# Commodore_CPM_Modul.net
KiCad netlist of a schematic drawn in Altium Designer
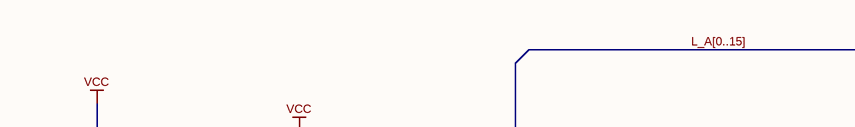
[diagram p0: Commodore CPM Modul.SchDoc, top left]
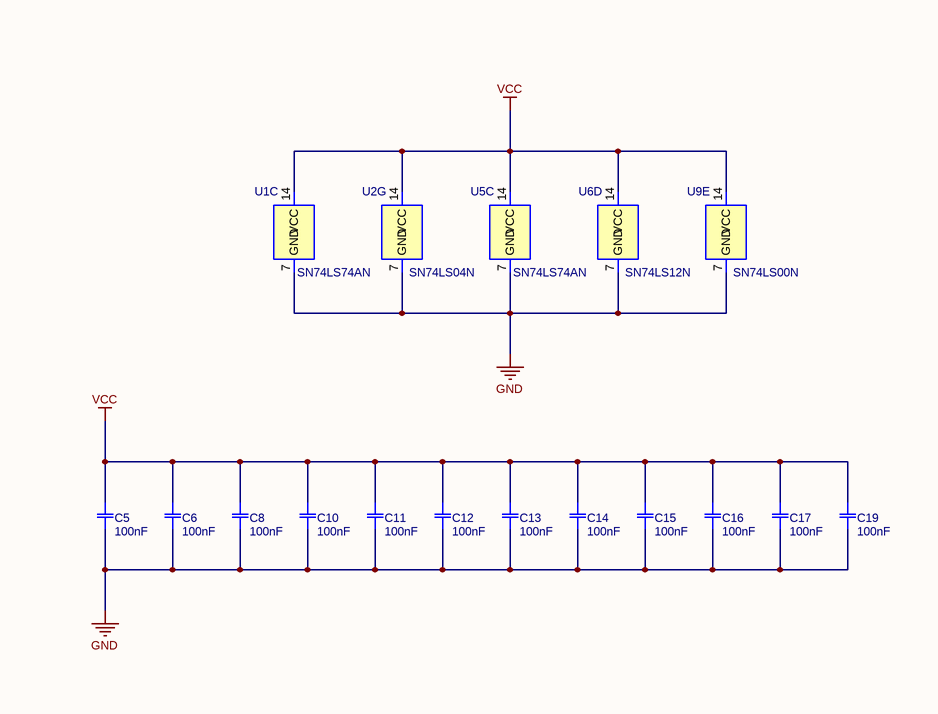
[diagram p1: Commodore CPM Modul.SchDoc, top right]
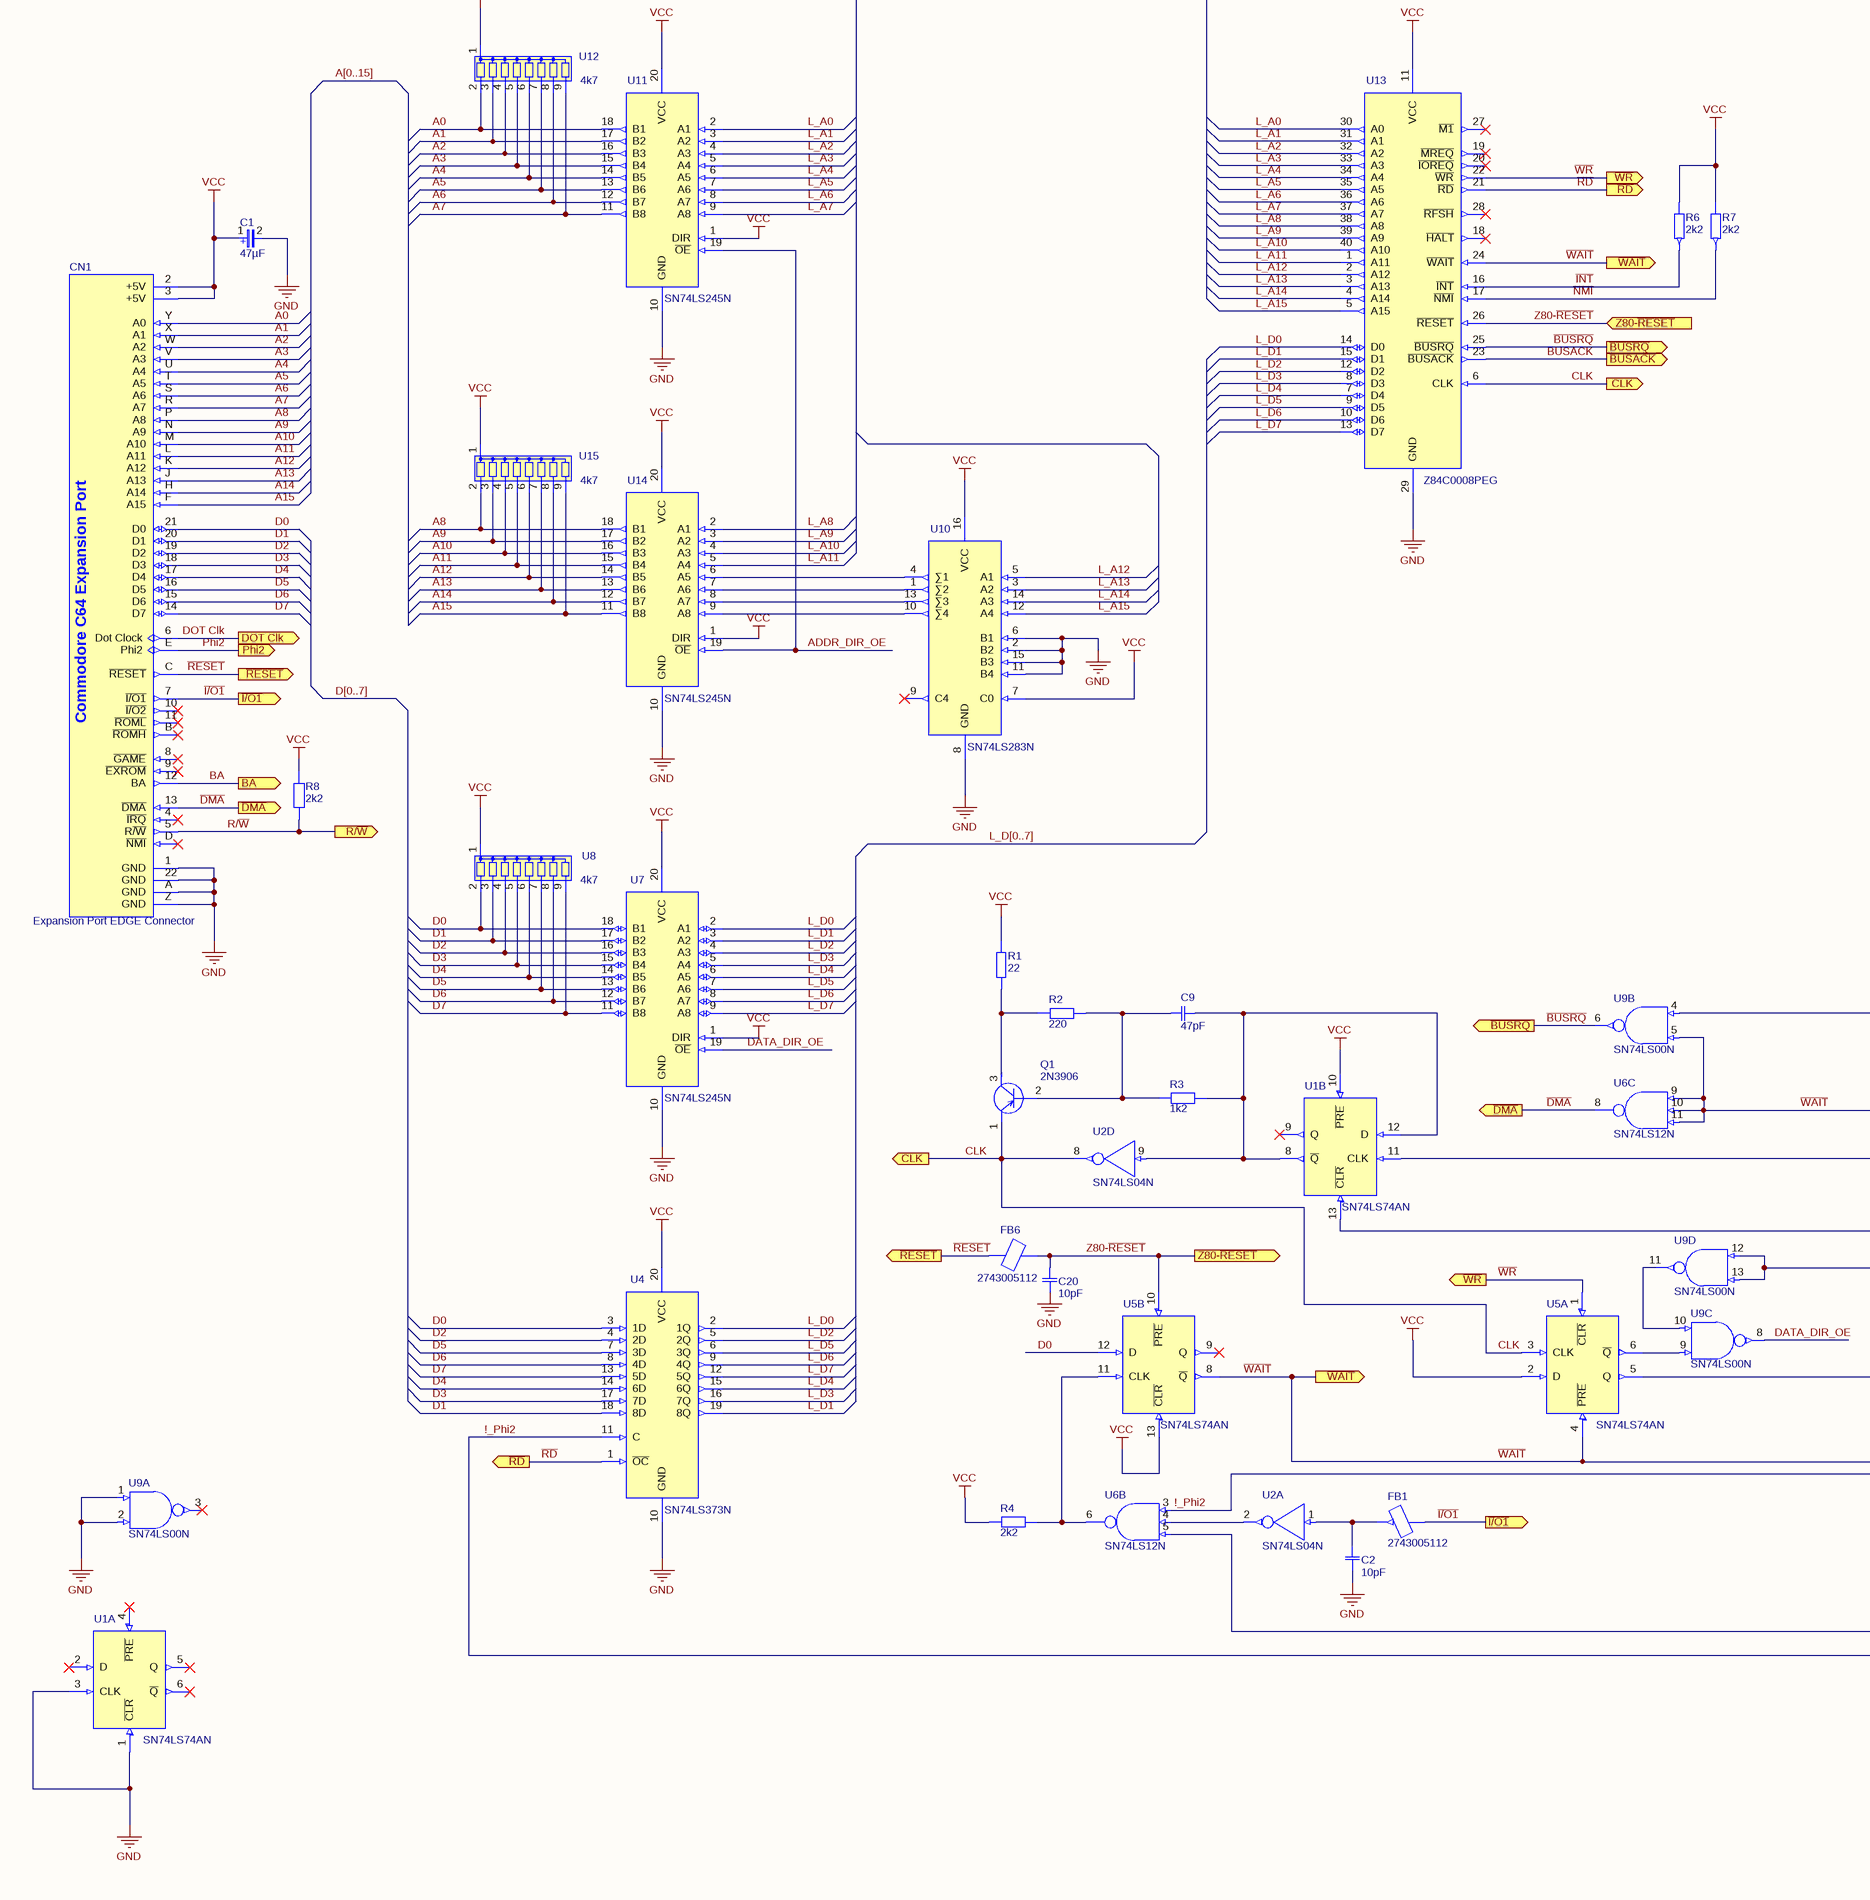
[diagram p2: Commodore CPM Modul.SchDoc, bottom left]
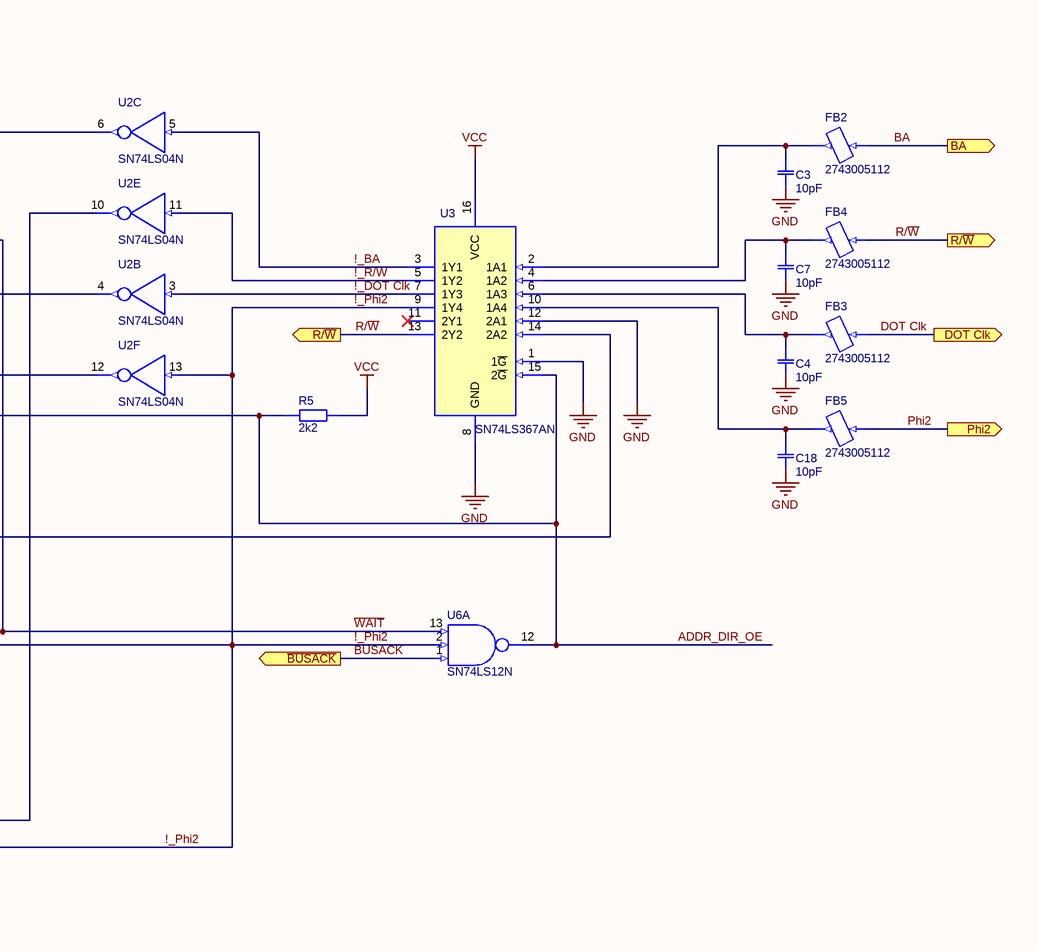
[diagram p3: Commodore CPM Modul.SchDoc, bottom right]

(export (version "E")
  (design (tool "Eeschema 10.0.6"))
  (components
    (comp (ref "C1")
      (value "47µF")
      (footprint "CAP Elec 47uF 25V Axial - Vishay MAL203036479E3")
      (description "Cap Aluminum 47uF 25V -10% to 50% (6 X 10mm) Axial 4.8 Ohm 100mA 3000 hr 85C Taped in Box")
      (fields (field (name "VOLTAGE") "25V") (field (name "TOLERANCE") "50%"))
      (libsource (lib "PCB-Tech Cloud") (part "Polarized Capacitor"))
    )
    (comp (ref "C2")
      (value "10pF")
      (footprint "CAP CER 10PF 50V C0G/NP0 AXIAL Vishay A100J15C0GF5TAA")
      (description "Cap Ceramic 10pF 50V C0G 5% Axial 125C T/R")
      (fields (field (name "TOLERANCE") "5%"))
      (libsource (lib "PCB-Tech Cloud") (part "Capacitor"))
    )
    (comp (ref "C3")
      (value "10pF")
      (footprint "CAP CER 10PF 50V C0G/NP0 AXIAL Vishay A100J15C0GF5TAA")
      (description "Cap Ceramic 10pF 50V C0G 5% Axial 125C T/R")
      (fields (field (name "TOLERANCE") "5%"))
      (libsource (lib "PCB-Tech Cloud") (part "Capacitor"))
    )
    (comp (ref "C4")
      (value "10pF")
      (footprint "CAP CER 10PF 50V C0G/NP0 AXIAL Vishay A100J15C0GF5TAA")
      (description "Cap Ceramic 10pF 50V C0G 5% Axial 125C T/R")
      (fields (field (name "TOLERANCE") "5%"))
      (libsource (lib "PCB-Tech Cloud") (part "Capacitor"))
    )
    (comp (ref "C5")
      (value "100nF")
      (footprint "CAP CER 0.1UF 50V X7R RADIAL Kemet C330C104J5R5TA")
      (description "Cap Ceramic 0.1uF 50V X7R 5% Radial 5.08mm 125C Bulk")
      (fields (field (name "TOLERANCE") "5%"))
      (libsource (lib "PCB-Tech Cloud") (part "Capacitor"))
    )
    (comp (ref "C6")
      (value "100nF")
      (footprint "CAP CER 0.1UF 50V X7R RADIAL Kemet C330C104J5R5TA")
      (description "Cap Ceramic 0.1uF 50V X7R 5% Radial 5.08mm 125C Bulk")
      (fields (field (name "TOLERANCE") "5%"))
      (libsource (lib "PCB-Tech Cloud") (part "Capacitor"))
    )
    (comp (ref "C7")
      (value "10pF")
      (footprint "CAP CER 10PF 50V C0G/NP0 AXIAL Vishay A100J15C0GF5TAA")
      (description "Cap Ceramic 10pF 50V C0G 5% Axial 125C T/R")
      (fields (field (name "TOLERANCE") "5%"))
      (libsource (lib "PCB-Tech Cloud") (part "Capacitor"))
    )
    (comp (ref "C8")
      (value "100nF")
      (footprint "CAP CER 0.1UF 50V X7R RADIAL Kemet C330C104J5R5TA")
      (description "Cap Ceramic 0.1uF 50V X7R 5% Radial 5.08mm 125C Bulk")
      (fields (field (name "TOLERANCE") "5%"))
      (libsource (lib "PCB-Tech Cloud") (part "Capacitor"))
    )
    (comp (ref "C9")
      (value "47pF")
      (footprint "CAP CER 47PF 50V C0G/NP0 AXIAL Vishay A470J15C0GF5TAA")
      (description "Cap Ceramic 47pF 50V C0G 5% Axial 125C T/R")
      (fields (field (name "TOLERANCE") "5%"))
      (libsource (lib "PCB-Tech Cloud") (part "Capacitor"))
    )
    (comp (ref "C10")
      (value "100nF")
      (footprint "CAP CER 0.1UF 50V X7R RADIAL Kemet C330C104J5R5TA")
      (description "Cap Ceramic 0.1uF 50V X7R 5% Radial 5.08mm 125C Bulk")
      (fields (field (name "TOLERANCE") "5%"))
      (libsource (lib "PCB-Tech Cloud") (part "Capacitor"))
    )
    (comp (ref "C11")
      (value "100nF")
      (footprint "CAP CER 0.1UF 50V X7R RADIAL Kemet C330C104J5R5TA")
      (description "Cap Ceramic 0.1uF 50V X7R 5% Radial 5.08mm 125C Bulk")
      (fields (field (name "TOLERANCE") "5%"))
      (libsource (lib "PCB-Tech Cloud") (part "Capacitor"))
    )
    (comp (ref "C12")
      (value "100nF")
      (footprint "CAP CER 0.1UF 50V X7R RADIAL Kemet C330C104J5R5TA")
      (description "Cap Ceramic 0.1uF 50V X7R 5% Radial 5.08mm 125C Bulk")
      (fields (field (name "TOLERANCE") "5%"))
      (libsource (lib "PCB-Tech Cloud") (part "Capacitor"))
    )
    (comp (ref "C13")
      (value "100nF")
      (footprint "CAP CER 0.1UF 50V X7R RADIAL Kemet C330C104J5R5TA")
      (description "Cap Ceramic 0.1uF 50V X7R 5% Radial 5.08mm 125C Bulk")
      (fields (field (name "TOLERANCE") "5%"))
      (libsource (lib "PCB-Tech Cloud") (part "Capacitor"))
    )
    (comp (ref "C14")
      (value "100nF")
      (footprint "CAP CER 0.1UF 50V X7R RADIAL Kemet C330C104J5R5TA")
      (description "Cap Ceramic 0.1uF 50V X7R 5% Radial 5.08mm 125C Bulk")
      (fields (field (name "TOLERANCE") "5%"))
      (libsource (lib "PCB-Tech Cloud") (part "Capacitor"))
    )
    (comp (ref "C15")
      (value "100nF")
      (footprint "CAP CER 0.1UF 50V X7R RADIAL Kemet C330C104J5R5TA")
      (description "Cap Ceramic 0.1uF 50V X7R 5% Radial 5.08mm 125C Bulk")
      (fields (field (name "TOLERANCE") "5%"))
      (libsource (lib "PCB-Tech Cloud") (part "Capacitor"))
    )
    (comp (ref "C16")
      (value "100nF")
      (footprint "CAP CER 0.1UF 50V X7R RADIAL Kemet C330C104J5R5TA")
      (description "Cap Ceramic 0.1uF 50V X7R 5% Radial 5.08mm 125C Bulk")
      (fields (field (name "TOLERANCE") "5%"))
      (libsource (lib "PCB-Tech Cloud") (part "Capacitor"))
    )
    (comp (ref "C17")
      (value "100nF")
      (footprint "CAP CER 0.1UF 50V X7R RADIAL Kemet C330C104J5R5TA")
      (description "Cap Ceramic 0.1uF 50V X7R 5% Radial 5.08mm 125C Bulk")
      (fields (field (name "TOLERANCE") "5%"))
      (libsource (lib "PCB-Tech Cloud") (part "Capacitor"))
    )
    (comp (ref "C18")
      (value "10pF")
      (footprint "CAP CER 10PF 50V C0G/NP0 AXIAL Vishay A100J15C0GF5TAA")
      (description "Cap Ceramic 10pF 50V C0G 5% Axial 125C T/R")
      (fields (field (name "TOLERANCE") "5%"))
      (libsource (lib "PCB-Tech Cloud") (part "Capacitor"))
    )
    (comp (ref "C19")
      (value "100nF")
      (footprint "CAP CER 0.1UF 50V X7R RADIAL Kemet C330C104J5R5TA")
      (description "Cap Ceramic 0.1uF 50V X7R 5% Radial 5.08mm 125C Bulk")
      (fields (field (name "TOLERANCE") "5%"))
      (libsource (lib "PCB-Tech Cloud") (part "Capacitor"))
    )
    (comp (ref "C20")
      (value "10pF")
      (footprint "CAP CER 10PF 50V C0G/NP0 AXIAL Vishay A100J15C0GF5TAA")
      (description "Cap Ceramic 10pF 50V C0G 5% Axial 125C T/R")
      (fields (field (name "TOLERANCE") "5%"))
      (libsource (lib "PCB-Tech Cloud") (part "Capacitor"))
    )
    (comp (ref "CN1")
      (value "Expansion Port EDGE Connector")
      (footprint "C64 Expansion Port EDGE Connector")
      (description "Expansion Port EDGE Connector for Interface Cards")
      (libsource (lib "PCB-Tech Cloud") (part "C64 Expansion Port"))
    )
    (comp (ref "FB1")
      (value "2743005112")
      (footprint "Ferrite Bead Fair Rite 2743005112 axial 10,16mm")
      (description "Ferrite Beads Axial 91Ohm 100MHz T/R")
      (libsource (lib "PCB-Tech Cloud") (part "Ferrite Bead"))
    )
    (comp (ref "FB2")
      (value "2743005112")
      (footprint "Ferrite Bead Fair Rite 2743005112 axial 10,16mm")
      (description "Ferrite Beads Axial 91Ohm 100MHz T/R")
      (libsource (lib "PCB-Tech Cloud") (part "Ferrite Bead"))
    )
    (comp (ref "FB3")
      (value "2743005112")
      (footprint "Ferrite Bead Fair Rite 2743005112 axial 10,16mm")
      (description "Ferrite Beads Axial 91Ohm 100MHz T/R")
      (libsource (lib "PCB-Tech Cloud") (part "Ferrite Bead"))
    )
    (comp (ref "FB4")
      (value "2743005112")
      (footprint "Ferrite Bead Fair Rite 2743005112 axial 10,16mm")
      (description "Ferrite Beads Axial 91Ohm 100MHz T/R")
      (libsource (lib "PCB-Tech Cloud") (part "Ferrite Bead"))
    )
    (comp (ref "FB5")
      (value "2743005112")
      (footprint "Ferrite Bead Fair Rite 2743005112 axial 10,16mm")
      (description "Ferrite Beads Axial 91Ohm 100MHz T/R")
      (libsource (lib "PCB-Tech Cloud") (part "Ferrite Bead"))
    )
    (comp (ref "FB6")
      (value "2743005112")
      (footprint "Ferrite Bead Fair Rite 2743005112 axial 10,16mm")
      (description "Ferrite Beads Axial 91Ohm 100MHz T/R")
      (libsource (lib "PCB-Tech Cloud") (part "Ferrite Bead"))
    )
    (comp (ref "Q1")
      (value "2N3906")
      (footprint "2N3906")
      (description "Bipolar Transistor PNP Amplifier/Switch 40V 200mA 3-Pin TO-92 Through Hole Box")
      (libsource (lib "PCB-Tech Cloud") (part "Transistor PNP EBC"))
    )
    (comp (ref "R1")
      (value "22")
      (footprint "22 Ohm R Axial DIN0207 L6.3mm D2.5mm P10.16mm Horizontal")
      (description "RES 22 OHM 1/4W 5% AXIAL")
      (fields (field (name "TOLERANCE") "5%"))
      (libsource (lib "PCB-Tech Cloud") (part "Resistor"))
    )
    (comp (ref "R2")
      (value "220")
      (footprint "220 Ohm R Axial DIN0207 L6.3mm D2.5mm P10.16mm Horizontal")
      (description "RES 220 OHM 1/4W 5% AXIAL")
      (fields (field (name "TOLERANCE") "5%"))
      (libsource (lib "PCB-Tech Cloud") (part "Resistor"))
    )
    (comp (ref "R3")
      (value "1k2")
      (footprint "1,2 kOhm R Axial DIN0207 L6.3mm D2.5mm P10.16mm Horizontal")
      (description "RES 1.2K OHM 1/4W 5% AXIAL")
      (fields (field (name "TOLERANCE") "5%"))
      (libsource (lib "PCB-Tech Cloud") (part "Resistor"))
    )
    (comp (ref "R4")
      (value "2k2")
      (footprint "2,2 kOhm R Axial DIN0207 L6.3mm D2.5mm P10.16mm Horizontal")
      (description "RES 2.2K OHM 1/4W 5% AXIAL")
      (fields (field (name "TOLERANCE") "5%"))
      (libsource (lib "PCB-Tech Cloud") (part "Resistor"))
    )
    (comp (ref "R5")
      (value "2k2")
      (footprint "2,2 kOhm R Axial DIN0207 L6.3mm D2.5mm P10.16mm Horizontal")
      (description "RES 2.2K OHM 1/4W 5% AXIAL")
      (fields (field (name "TOLERANCE") "5%"))
      (libsource (lib "PCB-Tech Cloud") (part "Resistor"))
    )
    (comp (ref "R6")
      (value "2k2")
      (footprint "2,2 kOhm R Axial DIN0207 L6.3mm D2.5mm P10.16mm Horizontal")
      (description "RES 2.2K OHM 1/4W 5% AXIAL")
      (fields (field (name "TOLERANCE") "5%"))
      (libsource (lib "PCB-Tech Cloud") (part "Resistor"))
    )
    (comp (ref "R7")
      (value "2k2")
      (footprint "2,2 kOhm R Axial DIN0207 L6.3mm D2.5mm P10.16mm Horizontal")
      (description "RES 2.2K OHM 1/4W 5% AXIAL")
      (fields (field (name "TOLERANCE") "5%"))
      (libsource (lib "PCB-Tech Cloud") (part "Resistor"))
    )
    (comp (ref "R8")
      (value "2k2")
      (footprint "2,2 kOhm R Axial DIN0207 L6.3mm D2.5mm P10.16mm Horizontal")
      (description "RES 2.2K OHM 1/4W 5% AXIAL")
      (fields (field (name "TOLERANCE") "5%"))
      (libsource (lib "PCB-Tech Cloud") (part "Resistor"))
    )
    (comp (ref "U1")
      (value "SN74LS74AN")
      (footprint "SN74LS74N with Socket")
      (libsource (lib "") (part "74xx74_1"))
    )
    (comp (ref "U2")
      (value "SN74LS04N")
      (footprint "SN74LS04N with Socket")
      (description "IC HEX INVERTER 14-DIP")
      (libsource (lib "PCB-Tech Cloud") (part "74xx04"))
    )
    (comp (ref "U3")
      (value "SN74LS367AN")
      (footprint "SN74LS367A with Socket")
      (description "I.C. SN74LS 367 AN")
      (libsource (lib "PCB-Tech Cloud") (part "74xx367"))
    )
    (comp (ref "U4")
      (value "SN74LS373N")
      (footprint "SN74LS373N with Socket")
      (description "Latch Transparent 3-ST 8-CH D-Type 20-Pin PDIP Tube")
      (libsource (lib "PCB-Tech Cloud") (part "74xx373"))
    )
    (comp (ref "U5")
      (value "SN74LS74AN")
      (footprint "SN74LS74N with Socket")
      (libsource (lib "") (part "74xx74_2"))
    )
    (comp (ref "U6")
      (value "SN74LS12N")
      (footprint "SN74LS12N with Socket")
      (description "Logic Gates Triple 3-input Positive-NAND gates with open collector outputs 14-PDIP 0 to 70")
      (libsource (lib "") (part "74xx12_2"))
    )
    (comp (ref "U7")
      (value "SN74LS245N")
      (footprint "SN74LS245N with Socket")
      (description "IC TXRX NON-INVERT 5.25V 20DIP")
      (libsource (lib "PCB-Tech Cloud") (part "74xx245"))
    )
    (comp (ref "U8")
      (value "4k7")
      (footprint "4k7 x8 Resistor Array SIL Royal 9A472G")
      (description "Resistor Networks & Arrays 9pin 4.7Kohms 2% Bussed")
      (fields (field (name "TOLERANCE") "2%"))
      (libsource (lib "PCB-Tech Cloud") (part "Resistor Network x8"))
    )
    (comp (ref "U9")
      (value "SN74LS00N")
      (footprint "SN74LS00N with Socket")
      (description "IC, 74LS, 74LS00, DIP14, 5.25V")
      (libsource (lib "") (part "74xx00_1"))
    )
    (comp (ref "U10")
      (value "SN74LS283N")
      (footprint "SN74LS283N with Socket")
      (description "Binary Full Adder Single 4-Bit 16-Pin PDIP Box")
      (libsource (lib "PCB-Tech Cloud") (part "74xx283"))
    )
    (comp (ref "U11")
      (value "SN74LS245N")
      (footprint "SN74LS245N with Socket")
      (description "IC TXRX NON-INVERT 5.25V 20DIP")
      (libsource (lib "PCB-Tech Cloud") (part "74xx245"))
    )
    (comp (ref "U12")
      (value "4k7")
      (footprint "4k7 x8 Resistor Array SIL Royal 9A472G")
      (description "Resistor Networks & Arrays 9pin 4.7Kohms 2% Bussed")
      (fields (field (name "TOLERANCE") "2%"))
      (libsource (lib "PCB-Tech Cloud") (part "Resistor Network x8"))
    )
    (comp (ref "U13")
      (value "Z84C0008PEG")
      (footprint "Zilog Z80 CPU with Socket")
      (description "IC MPU Z80 8MHZ 40DIP")
      (fields (field (name "VOLTAGE") "5V"))
      (libsource (lib "PCB-Tech Cloud") (part "Zilog Z80 CPU"))
    )
    (comp (ref "U14")
      (value "SN74LS245N")
      (footprint "SN74LS245N with Socket")
      (description "IC TXRX NON-INVERT 5.25V 20DIP")
      (libsource (lib "PCB-Tech Cloud") (part "74xx245"))
    )
    (comp (ref "U15")
      (value "4k7")
      (footprint "4k7 x8 Resistor Array SIL Royal 9A472G")
      (description "Resistor Networks & Arrays 9pin 4.7Kohms 2% Bussed")
      (fields (field (name "TOLERANCE") "2%"))
      (libsource (lib "PCB-Tech Cloud") (part "Resistor Network x8"))
    )
  )
  (nets
    (net (code "1") (name "/!_BA") (class "Default")
      (node (ref "U2") (pin "5") (pinfunction "3A_5") (pintype "input"))
      (node (ref "U3") (pin "3") (pinfunction "1Y1_3") (pintype "open_collector"))
    )
    (net (code "2") (name "/!_DOT Clk") (class "Default")
      (node (ref "U2") (pin "3") (pinfunction "2A_3") (pintype "input"))
      (node (ref "U3") (pin "7") (pinfunction "1Y3_7") (pintype "open_collector"))
    )
    (net (code "3") (name "/!_Phi2") (class "Default")
      (node (ref "U2") (pin "13") (pinfunction "6A_13") (pintype "input"))
      (node (ref "U3") (pin "9") (pinfunction "1Y4_9") (pintype "open_collector"))
      (node (ref "U4") (pin "11") (pinfunction "C_11") (pintype "input"))
      (node (ref "U6") (pin "2") (pinfunction "1B_2") (pintype "input"))
      (node (ref "U6") (pin "3") (pinfunction "2A_3") (pintype "input"))
    )
    (net (code "4") (name "/!_R{slash}~{W}") (class "Default")
      (node (ref "U2") (pin "11") (pinfunction "5A_11") (pintype "input"))
      (node (ref "U3") (pin "5") (pinfunction "1Y2_5") (pintype "open_collector"))
    )
    (net (code "5") (name "/A0") (class "Default")
      (node (ref "CN1") (pin "Y") (pinfunction "A0_Y") (pintype "input"))
      (node (ref "U11") (pin "18") (pinfunction "B1_18") (pintype "output"))
      (node (ref "U12") (pin "2") (pinfunction "2_2") (pintype "passive"))
    )
    (net (code "6") (name "/A1") (class "Default")
      (node (ref "CN1") (pin "X") (pinfunction "A1_X") (pintype "input"))
      (node (ref "U11") (pin "17") (pinfunction "B2_17") (pintype "output"))
      (node (ref "U12") (pin "3") (pinfunction "3_3") (pintype "passive"))
    )
    (net (code "7") (name "/A2") (class "Default")
      (node (ref "CN1") (pin "W") (pinfunction "A2_W") (pintype "input"))
      (node (ref "U11") (pin "16") (pinfunction "B3_16") (pintype "output"))
      (node (ref "U12") (pin "4") (pinfunction "4_4") (pintype "passive"))
    )
    (net (code "8") (name "/A3") (class "Default")
      (node (ref "CN1") (pin "V") (pinfunction "A3_V") (pintype "input"))
      (node (ref "U11") (pin "15") (pinfunction "B4_15") (pintype "output"))
      (node (ref "U12") (pin "5") (pinfunction "5_5") (pintype "passive"))
    )
    (net (code "9") (name "/A4") (class "Default")
      (node (ref "CN1") (pin "U") (pinfunction "A4_U") (pintype "input"))
      (node (ref "U11") (pin "14") (pinfunction "B5_14") (pintype "output"))
      (node (ref "U12") (pin "6") (pinfunction "6_6") (pintype "passive"))
    )
    (net (code "10") (name "/A5") (class "Default")
      (node (ref "CN1") (pin "T") (pinfunction "A5_T") (pintype "input"))
      (node (ref "U11") (pin "13") (pinfunction "B6_13") (pintype "output"))
      (node (ref "U12") (pin "7") (pinfunction "7_7") (pintype "passive"))
    )
    (net (code "11") (name "/A6") (class "Default")
      (node (ref "CN1") (pin "S") (pinfunction "A6_S") (pintype "input"))
      (node (ref "U11") (pin "12") (pinfunction "B7_12") (pintype "output"))
      (node (ref "U12") (pin "8") (pinfunction "8_8") (pintype "passive"))
    )
    (net (code "12") (name "/A7") (class "Default")
      (node (ref "CN1") (pin "R") (pinfunction "A7_R") (pintype "input"))
      (node (ref "U11") (pin "11") (pinfunction "B8_11") (pintype "output"))
      (node (ref "U12") (pin "9") (pinfunction "9_9") (pintype "passive"))
    )
    (net (code "13") (name "/A8") (class "Default")
      (node (ref "CN1") (pin "P") (pinfunction "A8_P") (pintype "input"))
      (node (ref "U14") (pin "18") (pinfunction "B1_18") (pintype "output"))
      (node (ref "U15") (pin "2") (pinfunction "2_2") (pintype "passive"))
    )
    (net (code "14") (name "/A9") (class "Default")
      (node (ref "CN1") (pin "N") (pinfunction "A9_N") (pintype "input"))
      (node (ref "U14") (pin "17") (pinfunction "B2_17") (pintype "output"))
      (node (ref "U15") (pin "3") (pinfunction "3_3") (pintype "passive"))
    )
    (net (code "15") (name "/A10") (class "Default")
      (node (ref "CN1") (pin "M") (pinfunction "A10_M") (pintype "input"))
      (node (ref "U14") (pin "16") (pinfunction "B3_16") (pintype "output"))
      (node (ref "U15") (pin "4") (pinfunction "4_4") (pintype "passive"))
    )
    (net (code "16") (name "/A11") (class "Default")
      (node (ref "CN1") (pin "L") (pinfunction "A11_L") (pintype "input"))
      (node (ref "U14") (pin "15") (pinfunction "B4_15") (pintype "output"))
      (node (ref "U15") (pin "5") (pinfunction "5_5") (pintype "passive"))
    )
    (net (code "17") (name "/A12") (class "Default")
      (node (ref "CN1") (pin "K") (pinfunction "A12_K") (pintype "input"))
      (node (ref "U14") (pin "14") (pinfunction "B5_14") (pintype "output"))
      (node (ref "U15") (pin "6") (pinfunction "6_6") (pintype "passive"))
    )
    (net (code "18") (name "/A13") (class "Default")
      (node (ref "CN1") (pin "J") (pinfunction "A13_J") (pintype "input"))
      (node (ref "U14") (pin "13") (pinfunction "B6_13") (pintype "output"))
      (node (ref "U15") (pin "7") (pinfunction "7_7") (pintype "passive"))
    )
    (net (code "19") (name "/A14") (class "Default")
      (node (ref "CN1") (pin "H") (pinfunction "A14_H") (pintype "input"))
      (node (ref "U14") (pin "12") (pinfunction "B7_12") (pintype "output"))
      (node (ref "U15") (pin "8") (pinfunction "8_8") (pintype "passive"))
    )
    (net (code "20") (name "/A15") (class "Default")
      (node (ref "CN1") (pin "F") (pinfunction "A15_F") (pintype "input"))
      (node (ref "U14") (pin "11") (pinfunction "B8_11") (pintype "output"))
      (node (ref "U15") (pin "9") (pinfunction "9_9") (pintype "passive"))
    )
    (net (code "21") (name "/ADDR_DIR_OE") (class "Default")
      (node (ref "R5") (pin "1") (pinfunction "1_1") (pintype "passive"))
      (node (ref "U11") (pin "19") (pinfunction "~{OE}_19") (pintype "input"))
      (node (ref "U14") (pin "19") (pinfunction "~{OE}_19") (pintype "input"))
      (node (ref "U3") (pin "15") (pinfunction "2~{G}_15") (pintype "input"))
      (node (ref "U6") (pin "12") (pinfunction "1Y_12") (pintype "open_collector"))
      (node (ref "U9") (pin "12") (pinfunction "4B_12") (pintype "input"))
      (node (ref "U9") (pin "13") (pinfunction "4A_13") (pintype "input"))
    )
    (net (code "23") (name "/BA") (class "Default")
      (node (ref "CN1") (pin "12") (pinfunction "BA_12") (pintype "output"))
      (node (ref "FB2") (pin "1") (pinfunction "1_1") (pintype "passive"))
    )
    (net (code "24") (name "/CLK") (class "Default")
      (node (ref "Q1") (pin "1") (pinfunction "1_1") (pintype "passive"))
      (node (ref "U13") (pin "6") (pinfunction "CLK_6") (pintype "input"))
      (node (ref "U2") (pin "8") (pinfunction "4Y_8") (pintype "output"))
      (node (ref "U5") (pin "3") (pinfunction "CLK_3") (pintype "input"))
    )
    (net (code "25") (name "/D0") (class "Default")
      (node (ref "CN1") (pin "21") (pinfunction "D0_21") (pintype "bidirectional"))
      (node (ref "U4") (pin "3") (pinfunction "1D_3") (pintype "input"))
      (node (ref "U5") (pin "12") (pinfunction "D_12") (pintype "input"))
      (node (ref "U7") (pin "18") (pinfunction "B1_18") (pintype "output"))
      (node (ref "U8") (pin "2") (pinfunction "2_2") (pintype "passive"))
    )
    (net (code "26") (name "/D1") (class "Default")
      (node (ref "CN1") (pin "20") (pinfunction "D1_20") (pintype "bidirectional"))
      (node (ref "U4") (pin "18") (pinfunction "8D_18") (pintype "input"))
      (node (ref "U7") (pin "17") (pinfunction "B2_17") (pintype "output"))
      (node (ref "U8") (pin "3") (pinfunction "3_3") (pintype "passive"))
    )
    (net (code "27") (name "/D2") (class "Default")
      (node (ref "CN1") (pin "19") (pinfunction "D2_19") (pintype "bidirectional"))
      (node (ref "U4") (pin "4") (pinfunction "2D_4") (pintype "input"))
      (node (ref "U7") (pin "16") (pinfunction "B3_16") (pintype "output"))
      (node (ref "U8") (pin "4") (pinfunction "4_4") (pintype "passive"))
    )
    (net (code "28") (name "/D3") (class "Default")
      (node (ref "CN1") (pin "18") (pinfunction "D3_18") (pintype "bidirectional"))
      (node (ref "U4") (pin "17") (pinfunction "7D_17") (pintype "input"))
      (node (ref "U7") (pin "15") (pinfunction "B4_15") (pintype "output"))
      (node (ref "U8") (pin "5") (pinfunction "5_5") (pintype "passive"))
    )
    (net (code "29") (name "/D4") (class "Default")
      (node (ref "CN1") (pin "17") (pinfunction "D4_17") (pintype "bidirectional"))
      (node (ref "U4") (pin "14") (pinfunction "6D_14") (pintype "input"))
      (node (ref "U7") (pin "14") (pinfunction "B5_14") (pintype "output"))
      (node (ref "U8") (pin "6") (pinfunction "6_6") (pintype "passive"))
    )
    (net (code "30") (name "/D5") (class "Default")
      (node (ref "CN1") (pin "16") (pinfunction "D5_16") (pintype "bidirectional"))
      (node (ref "U4") (pin "7") (pinfunction "3D_7") (pintype "input"))
      (node (ref "U7") (pin "13") (pinfunction "B6_13") (pintype "output"))
      (node (ref "U8") (pin "7") (pinfunction "7_7") (pintype "passive"))
    )
    (net (code "31") (name "/D6") (class "Default")
      (node (ref "CN1") (pin "15") (pinfunction "D6_15") (pintype "bidirectional"))
      (node (ref "U4") (pin "8") (pinfunction "4D_8") (pintype "input"))
      (node (ref "U7") (pin "12") (pinfunction "B7_12") (pintype "output"))
      (node (ref "U8") (pin "8") (pinfunction "8_8") (pintype "passive"))
    )
    (net (code "32") (name "/D7") (class "Default")
      (node (ref "CN1") (pin "14") (pinfunction "D7_14") (pintype "bidirectional"))
      (node (ref "U4") (pin "13") (pinfunction "5D_13") (pintype "input"))
      (node (ref "U7") (pin "11") (pinfunction "B8_11") (pintype "output"))
      (node (ref "U8") (pin "9") (pinfunction "9_9") (pintype "passive"))
    )
    (net (code "33") (name "/DATA_DIR_OE") (class "Default")
      (node (ref "U7") (pin "19") (pinfunction "~{OE}_19") (pintype "input"))
      (node (ref "U9") (pin "8") (pinfunction "3Y_8") (pintype "output"))
    )
    (net (code "34") (name "/DOT Clk") (class "Default")
      (node (ref "CN1") (pin "6") (pinfunction "Dot_Clock_6") (pintype "output"))
      (node (ref "FB3") (pin "1") (pinfunction "1_1") (pintype "passive"))
    )
    (net (code "36") (name "/L_A0") (class "Default")
      (node (ref "U11") (pin "2") (pinfunction "A1_2") (pintype "input"))
      (node (ref "U13") (pin "30") (pinfunction "A0_30") (pintype "output"))
    )
    (net (code "37") (name "/L_A1") (class "Default")
      (node (ref "U11") (pin "3") (pinfunction "A2_3") (pintype "input"))
      (node (ref "U13") (pin "31") (pinfunction "A1_31") (pintype "output"))
    )
    (net (code "38") (name "/L_A2") (class "Default")
      (node (ref "U11") (pin "4") (pinfunction "A3_4") (pintype "input"))
      (node (ref "U13") (pin "32") (pinfunction "A2_32") (pintype "output"))
    )
    (net (code "39") (name "/L_A3") (class "Default")
      (node (ref "U11") (pin "5") (pinfunction "A4_5") (pintype "input"))
      (node (ref "U13") (pin "33") (pinfunction "A3_33") (pintype "output"))
    )
    (net (code "40") (name "/L_A4") (class "Default")
      (node (ref "U11") (pin "6") (pinfunction "A5_6") (pintype "input"))
      (node (ref "U13") (pin "34") (pinfunction "A4_34") (pintype "output"))
    )
    (net (code "41") (name "/L_A5") (class "Default")
      (node (ref "U11") (pin "7") (pinfunction "A6_7") (pintype "input"))
      (node (ref "U13") (pin "35") (pinfunction "A5_35") (pintype "output"))
    )
    (net (code "42") (name "/L_A6") (class "Default")
      (node (ref "U11") (pin "8") (pinfunction "A7_8") (pintype "input"))
      (node (ref "U13") (pin "36") (pinfunction "A6_36") (pintype "output"))
    )
    (net (code "43") (name "/L_A7") (class "Default")
      (node (ref "U11") (pin "9") (pinfunction "A8_9") (pintype "input"))
      (node (ref "U13") (pin "37") (pinfunction "A7_37") (pintype "output"))
    )
    (net (code "44") (name "/L_A8") (class "Default")
      (node (ref "U13") (pin "38") (pinfunction "A8_38") (pintype "output"))
      (node (ref "U14") (pin "2") (pinfunction "A1_2") (pintype "input"))
    )
    (net (code "45") (name "/L_A9") (class "Default")
      (node (ref "U13") (pin "39") (pinfunction "A9_39") (pintype "output"))
      (node (ref "U14") (pin "3") (pinfunction "A2_3") (pintype "input"))
    )
    (net (code "46") (name "/L_A10") (class "Default")
      (node (ref "U13") (pin "40") (pinfunction "A10_40") (pintype "output"))
      (node (ref "U14") (pin "4") (pinfunction "A3_4") (pintype "input"))
    )
    (net (code "47") (name "/L_A11") (class "Default")
      (node (ref "U13") (pin "1") (pinfunction "A11_1") (pintype "output"))
      (node (ref "U14") (pin "5") (pinfunction "A4_5") (pintype "input"))
    )
    (net (code "48") (name "/L_A12") (class "Default")
      (node (ref "U10") (pin "5") (pinfunction "A1_5") (pintype "input"))
      (node (ref "U13") (pin "2") (pinfunction "A12_2") (pintype "output"))
    )
    (net (code "49") (name "/L_A13") (class "Default")
      (node (ref "U10") (pin "3") (pinfunction "A2_3") (pintype "input"))
      (node (ref "U13") (pin "3") (pinfunction "A13_3") (pintype "output"))
    )
    (net (code "50") (name "/L_A14") (class "Default")
      (node (ref "U10") (pin "14") (pinfunction "A3_14") (pintype "input"))
      (node (ref "U13") (pin "4") (pinfunction "A14_4") (pintype "output"))
    )
    (net (code "51") (name "/L_A15") (class "Default")
      (node (ref "U10") (pin "12") (pinfunction "A4_12") (pintype "input"))
      (node (ref "U13") (pin "5") (pinfunction "A15_5") (pintype "output"))
    )
    (net (code "53") (name "/L_D0") (class "Default")
      (node (ref "U13") (pin "14") (pinfunction "D0_14") (pintype "bidirectional"))
      (node (ref "U4") (pin "2") (pinfunction "1Q_2") (pintype "output"))
      (node (ref "U7") (pin "2") (pinfunction "A1_2") (pintype "input"))
    )
    (net (code "54") (name "/L_D1") (class "Default")
      (node (ref "U13") (pin "15") (pinfunction "D1_15") (pintype "bidirectional"))
      (node (ref "U4") (pin "19") (pinfunction "8Q_19") (pintype "output"))
      (node (ref "U7") (pin "3") (pinfunction "A2_3") (pintype "input"))
    )
    (net (code "55") (name "/L_D2") (class "Default")
      (node (ref "U13") (pin "12") (pinfunction "D2_12") (pintype "bidirectional"))
      (node (ref "U4") (pin "5") (pinfunction "2Q_5") (pintype "output"))
      (node (ref "U7") (pin "4") (pinfunction "A3_4") (pintype "input"))
    )
    (net (code "56") (name "/L_D3") (class "Default")
      (node (ref "U13") (pin "8") (pinfunction "D3_8") (pintype "bidirectional"))
      (node (ref "U4") (pin "16") (pinfunction "7Q_16") (pintype "output"))
      (node (ref "U7") (pin "5") (pinfunction "A4_5") (pintype "input"))
    )
    (net (code "57") (name "/L_D4") (class "Default")
      (node (ref "U13") (pin "7") (pinfunction "D4_7") (pintype "bidirectional"))
      (node (ref "U4") (pin "15") (pinfunction "6Q_15") (pintype "output"))
      (node (ref "U7") (pin "6") (pinfunction "A5_6") (pintype "input"))
    )
    (net (code "58") (name "/L_D5") (class "Default")
      (node (ref "U13") (pin "9") (pinfunction "D5_9") (pintype "bidirectional"))
      (node (ref "U4") (pin "6") (pinfunction "3Q_6") (pintype "output"))
      (node (ref "U7") (pin "7") (pinfunction "A6_7") (pintype "input"))
    )
    (net (code "59") (name "/L_D6") (class "Default")
      (node (ref "U13") (pin "10") (pinfunction "D6_10") (pintype "bidirectional"))
      (node (ref "U4") (pin "9") (pinfunction "4Q_9") (pintype "output"))
      (node (ref "U7") (pin "8") (pinfunction "A7_8") (pintype "input"))
    )
    (net (code "60") (name "/L_D7") (class "Default")
      (node (ref "U13") (pin "13") (pinfunction "D7_13") (pintype "bidirectional"))
      (node (ref "U4") (pin "12") (pinfunction "5Q_12") (pintype "output"))
      (node (ref "U7") (pin "9") (pinfunction "A8_9") (pintype "input"))
    )
    (net (code "62") (name "/Phi2") (class "Default")
      (node (ref "CN1") (pin "E") (pinfunction "Phi2_E") (pintype "output"))
      (node (ref "FB5") (pin "1") (pinfunction "1_1") (pintype "passive"))
    )
    (net (code "63") (name "/R{slash}~{W}") (class "Default")
      (node (ref "CN1") (pin "5") (pinfunction "R~{/W}_5") (pintype "output"))
      (node (ref "FB4") (pin "1") (pinfunction "1_1") (pintype "passive"))
      (node (ref "R8") (pin "2") (pinfunction "2_2") (pintype "passive"))
      (node (ref "U3") (pin "13") (pinfunction "2Y2_13") (pintype "passive"))
    )
    (net (code "64") (name "/Z80-~{RESET}") (class "Default")
      (node (ref "C20") (pin "2") (pinfunction "2_2") (pintype "passive"))
      (node (ref "FB6") (pin "2") (pinfunction "2_2") (pintype "passive"))
      (node (ref "U13") (pin "26") (pinfunction "~{RESET}_26") (pintype "input"))
      (node (ref "U5") (pin "10") (pinfunction "~{PRE}_10") (pintype "input"))
    )
    (net (code "65") (name "/~{BUSACK}") (class "Default")
      (node (ref "U13") (pin "23") (pinfunction "~{BUSACK}_23") (pintype "output"))
      (node (ref "U6") (pin "1") (pinfunction "1A_1") (pintype "input"))
    )
    (net (code "66") (name "/~{BUSRQ}") (class "Default")
      (node (ref "U13") (pin "25") (pinfunction "~{BUSRQ}_25") (pintype "input"))
      (node (ref "U9") (pin "6") (pinfunction "2Y_6") (pintype "output"))
    )
    (net (code "67") (name "/~{DMA}") (class "Default")
      (node (ref "CN1") (pin "13") (pinfunction "~{DMA}_13") (pintype "input"))
      (node (ref "U6") (pin "8") (pinfunction "3Y_8") (pintype "open_collector"))
    )
    (net (code "68") (name "/~{INT}") (class "Default")
      (node (ref "R6") (pin "2") (pinfunction "2_2") (pintype "passive"))
      (node (ref "U13") (pin "16") (pinfunction "~{INT}_16") (pintype "input"))
    )
    (net (code "69") (name "/~{I{slash}O1}") (class "Default")
      (node (ref "CN1") (pin "7") (pinfunction "~{I/O1}_7") (pintype "output"))
      (node (ref "FB1") (pin "1") (pinfunction "1_1") (pintype "passive"))
    )
    (net (code "70") (name "/~{NMI}") (class "Default")
      (node (ref "R7") (pin "2") (pinfunction "2_2") (pintype "passive"))
      (node (ref "U13") (pin "17") (pinfunction "~{NMI}_17") (pintype "input"))
    )
    (net (code "71") (name "/~{RD}") (class "Default")
      (node (ref "U13") (pin "21") (pinfunction "~{RD}_21") (pintype "output"))
      (node (ref "U4") (pin "1") (pinfunction "~{OC}_1") (pintype "input"))
    )
    (net (code "72") (name "/~{RESET}") (class "Default")
      (node (ref "CN1") (pin "C") (pinfunction "~{RESET}_C") (pintype "output"))
      (node (ref "FB6") (pin "1") (pinfunction "1_1") (pintype "passive"))
    )
    (net (code "73") (name "/~{WAIT}") (class "Default")
      (node (ref "U13") (pin "24") (pinfunction "~{WAIT}_24") (pintype "input"))
      (node (ref "U5") (pin "4") (pinfunction "~{PRE}_4") (pintype "input"))
      (node (ref "U5") (pin "8") (pinfunction "~{Q}_8") (pintype "output"))
      (node (ref "U6") (pin "10") (pinfunction "3C_10") (pintype "input"))
      (node (ref "U6") (pin "11") (pinfunction "3B_11") (pintype "input"))
      (node (ref "U6") (pin "13") (pinfunction "1C_13") (pintype "input"))
      (node (ref "U6") (pin "9") (pinfunction "3A_9") (pintype "input"))
      (node (ref "U9") (pin "5") (pinfunction "2B_5") (pintype "input"))
    )
    (net (code "74") (name "/~{WR}") (class "Default")
      (node (ref "U13") (pin "22") (pinfunction "~{WR}_22") (pintype "output"))
      (node (ref "U5") (pin "1") (pinfunction "~{CLR}_1") (pintype "input"))
    )
    (net (code "75") (name "GND") (class "Default")
      (node (ref "C1") (pin "2") (pinfunction "2_2") (pintype "passive"))
      (node (ref "C10") (pin "1") (pinfunction "1_1") (pintype "passive"))
      (node (ref "C11") (pin "1") (pinfunction "1_1") (pintype "passive"))
      (node (ref "C12") (pin "1") (pinfunction "1_1") (pintype "passive"))
      (node (ref "C13") (pin "1") (pinfunction "1_1") (pintype "passive"))
      (node (ref "C14") (pin "1") (pinfunction "1_1") (pintype "passive"))
      (node (ref "C15") (pin "1") (pinfunction "1_1") (pintype "passive"))
      (node (ref "C16") (pin "1") (pinfunction "1_1") (pintype "passive"))
      (node (ref "C17") (pin "1") (pinfunction "1_1") (pintype "passive"))
      (node (ref "C18") (pin "1") (pinfunction "1_1") (pintype "passive"))
      (node (ref "C19") (pin "1") (pinfunction "1_1") (pintype "passive"))
      (node (ref "C2") (pin "1") (pinfunction "1_1") (pintype "passive"))
      (node (ref "C20") (pin "1") (pinfunction "1_1") (pintype "passive"))
      (node (ref "C3") (pin "2") (pinfunction "2_2") (pintype "passive"))
      (node (ref "C4") (pin "2") (pinfunction "2_2") (pintype "passive"))
      (node (ref "C5") (pin "1") (pinfunction "1_1") (pintype "passive"))
      (node (ref "C6") (pin "1") (pinfunction "1_1") (pintype "passive"))
      (node (ref "C7") (pin "1") (pinfunction "1_1") (pintype "passive"))
      (node (ref "C8") (pin "1") (pinfunction "1_1") (pintype "passive"))
      (node (ref "CN1") (pin "1") (pinfunction "GND_1") (pintype "power_in"))
      (node (ref "CN1") (pin "22") (pinfunction "GND_22") (pintype "power_in"))
      (node (ref "CN1") (pin "A") (pinfunction "GND_A") (pintype "power_in"))
      (node (ref "CN1") (pin "Z") (pinfunction "GND_Z") (pintype "power_in"))
      (node (ref "U1") (pin "1") (pinfunction "~{CLR}_1") (pintype "input"))
      (node (ref "U1") (pin "3") (pinfunction "CLK_3") (pintype "input"))
      (node (ref "U1") (pin "7") (pinfunction "GND_7") (pintype "passive"))
      (node (ref "U10") (pin "11") (pinfunction "B4_11") (pintype "input"))
      (node (ref "U10") (pin "15") (pinfunction "B3_15") (pintype "input"))
      (node (ref "U10") (pin "2") (pinfunction "B2_2") (pintype "input"))
      (node (ref "U10") (pin "6") (pinfunction "B1_6") (pintype "input"))
      (node (ref "U10") (pin "8") (pinfunction "GND_8") (pintype "power_in"))
      (node (ref "U11") (pin "10") (pinfunction "GND_10") (pintype "passive"))
      (node (ref "U13") (pin "29") (pinfunction "GND_29") (pintype "power_in"))
      (node (ref "U14") (pin "10") (pinfunction "GND_10") (pintype "passive"))
      (node (ref "U2") (pin "7") (pinfunction "GND_7") (pintype "passive"))
      (node (ref "U3") (pin "1") (pinfunction "1~{G}_1") (pintype "input"))
      (node (ref "U3") (pin "12") (pinfunction "2A1_12") (pintype "input"))
      (node (ref "U3") (pin "8") (pinfunction "GND_8") (pintype "power_in"))
      (node (ref "U4") (pin "10") (pinfunction "GND_10") (pintype "power_in"))
      (node (ref "U5") (pin "7") (pinfunction "GND_7") (pintype "passive"))
      (node (ref "U6") (pin "7") (pinfunction "GND_7") (pintype "passive"))
      (node (ref "U7") (pin "10") (pinfunction "GND_10") (pintype "passive"))
      (node (ref "U9") (pin "1") (pinfunction "1A_1") (pintype "input"))
      (node (ref "U9") (pin "2") (pinfunction "1B_2") (pintype "input"))
      (node (ref "U9") (pin "7") (pinfunction "GND_7") (pintype "passive"))
    )
    (net (code "76") (name "Net-(C9-Pad2)") (class "Default")
      (node (ref "C9") (pin "2") (pinfunction "2_2") (pintype "passive"))
      (node (ref "Q1") (pin "2") (pinfunction "2_2") (pintype "passive"))
      (node (ref "R2") (pin "2") (pinfunction "2_2") (pintype "passive"))
      (node (ref "R3") (pin "1") (pinfunction "1_1") (pintype "passive"))
    )
    (net (code "77") (name "Net-(Q1-Pad3)") (class "Default")
      (node (ref "Q1") (pin "3") (pinfunction "3_3") (pintype "passive"))
      (node (ref "R1") (pin "1") (pinfunction "1_1") (pintype "passive"))
      (node (ref "R2") (pin "1") (pinfunction "1_1") (pintype "passive"))
    )
    (net (code "78") (name "Net-(U1B-CLK)") (class "Default")
      (node (ref "U1") (pin "11") (pinfunction "CLK_11") (pintype "input"))
      (node (ref "U2") (pin "4") (pinfunction "2Y_4") (pintype "output"))
    )
    (net (code "79") (name "Net-(U1B-D)") (class "Default")
      (node (ref "C9") (pin "1") (pinfunction "1_1") (pintype "passive"))
      (node (ref "R3") (pin "2") (pinfunction "2_2") (pintype "passive"))
      (node (ref "U1") (pin "12") (pinfunction "D_12") (pintype "input"))
      (node (ref "U1") (pin "8") (pinfunction "~{Q}_8") (pintype "output"))
      (node (ref "U2") (pin "9") (pinfunction "4A_9") (pintype "input"))
    )
    (net (code "80") (name "Net-(U1B-~{CLR})") (class "Default")
      (node (ref "U1") (pin "13") (pinfunction "~{CLR}_13") (pintype "input"))
      (node (ref "U2") (pin "12") (pinfunction "6Y_12") (pintype "output"))
    )
    (net (code "81") (name "Net-(U2A-1A)") (class "Default")
      (node (ref "C2") (pin "2") (pinfunction "2_2") (pintype "passive"))
      (node (ref "FB1") (pin "2") (pinfunction "2_2") (pintype "passive"))
      (node (ref "U2") (pin "1") (pinfunction "1A_1") (pintype "input"))
    )
    (net (code "82") (name "Net-(U2A-1Y)") (class "Default")
      (node (ref "U2") (pin "2") (pinfunction "1Y_2") (pintype "output"))
      (node (ref "U6") (pin "4") (pinfunction "2B_4") (pintype "input"))
    )
    (net (code "83") (name "Net-(U2C-3Y)") (class "Default")
      (node (ref "U2") (pin "6") (pinfunction "3Y_6") (pintype "output"))
      (node (ref "U9") (pin "4") (pinfunction "2A_4") (pintype "input"))
    )
    (net (code "84") (name "Net-(U2E-5Y)") (class "Default")
      (node (ref "U2") (pin "10") (pinfunction "5Y_10") (pintype "output"))
      (node (ref "U6") (pin "5") (pinfunction "2C_5") (pintype "input"))
    )
    (net (code "85") (name "Net-(U3-1A1)") (class "Default")
      (node (ref "C3") (pin "1") (pinfunction "1_1") (pintype "passive"))
      (node (ref "FB2") (pin "2") (pinfunction "2_2") (pintype "passive"))
      (node (ref "U3") (pin "2") (pinfunction "1A1_2") (pintype "input"))
    )
    (net (code "86") (name "Net-(U3-1A2)") (class "Default")
      (node (ref "C7") (pin "2") (pinfunction "2_2") (pintype "passive"))
      (node (ref "FB4") (pin "2") (pinfunction "2_2") (pintype "passive"))
      (node (ref "U3") (pin "4") (pinfunction "1A2_4") (pintype "input"))
    )
    (net (code "87") (name "Net-(U3-1A3)") (class "Default")
      (node (ref "C4") (pin "1") (pinfunction "1_1") (pintype "passive"))
      (node (ref "FB3") (pin "2") (pinfunction "2_2") (pintype "passive"))
      (node (ref "U3") (pin "6") (pinfunction "1A3_6") (pintype "input"))
    )
    (net (code "88") (name "Net-(U3-1A4)") (class "Default")
      (node (ref "C18") (pin "2") (pinfunction "2_2") (pintype "passive"))
      (node (ref "FB5") (pin "2") (pinfunction "2_2") (pintype "passive"))
      (node (ref "U3") (pin "10") (pinfunction "1A4_10") (pintype "input"))
    )
    (net (code "89") (name "Net-(U3-2A2)") (class "Default")
      (node (ref "U3") (pin "14") (pinfunction "2A2_14") (pintype "input"))
      (node (ref "U5") (pin "5") (pinfunction "Q_5") (pintype "output"))
    )
    (net (code "90") (name "Net-(U5A-~{Q})") (class "Default")
      (node (ref "U5") (pin "6") (pinfunction "~{Q}_6") (pintype "output"))
      (node (ref "U9") (pin "9") (pinfunction "3B_9") (pintype "input"))
    )
    (net (code "91") (name "Net-(U5B-CLK)") (class "Default")
      (node (ref "R4") (pin "1") (pinfunction "1_1") (pintype "passive"))
      (node (ref "U5") (pin "11") (pinfunction "CLK_11") (pintype "input"))
      (node (ref "U6") (pin "6") (pinfunction "2Y_6") (pintype "open_collector"))
    )
    (net (code "92") (name "Net-(U9C-3A)") (class "Default")
      (node (ref "U9") (pin "10") (pinfunction "3A_10") (pintype "input"))
      (node (ref "U9") (pin "11") (pinfunction "4Y_11") (pintype "output"))
    )
    (net (code "93") (name "Net-(U10-∑1)") (class "Default")
      (node (ref "U10") (pin "4") (pinfunction "∑1_4") (pintype "output"))
      (node (ref "U14") (pin "6") (pinfunction "A5_6") (pintype "input"))
    )
    (net (code "94") (name "Net-(U10-∑2)") (class "Default")
      (node (ref "U10") (pin "1") (pinfunction "∑2_1") (pintype "output"))
      (node (ref "U14") (pin "7") (pinfunction "A6_7") (pintype "input"))
    )
    (net (code "95") (name "Net-(U10-∑3)") (class "Default")
      (node (ref "U10") (pin "13") (pinfunction "∑3_13") (pintype "output"))
      (node (ref "U14") (pin "8") (pinfunction "A7_8") (pintype "input"))
    )
    (net (code "96") (name "Net-(U10-∑4)") (class "Default")
      (node (ref "U10") (pin "10") (pinfunction "∑4_10") (pintype "output"))
      (node (ref "U14") (pin "9") (pinfunction "A8_9") (pintype "input"))
    )
    (net (code "97") (name "VCC") (class "Default")
      (node (ref "C1") (pin "1") (pinfunction "1_1") (pintype "passive"))
      (node (ref "C10") (pin "2") (pinfunction "2_2") (pintype "passive"))
      (node (ref "C11") (pin "2") (pinfunction "2_2") (pintype "passive"))
      (node (ref "C12") (pin "2") (pinfunction "2_2") (pintype "passive"))
      (node (ref "C13") (pin "2") (pinfunction "2_2") (pintype "passive"))
      (node (ref "C14") (pin "2") (pinfunction "2_2") (pintype "passive"))
      (node (ref "C15") (pin "2") (pinfunction "2_2") (pintype "passive"))
      (node (ref "C16") (pin "2") (pinfunction "2_2") (pintype "passive"))
      (node (ref "C17") (pin "2") (pinfunction "2_2") (pintype "passive"))
      (node (ref "C19") (pin "2") (pinfunction "2_2") (pintype "passive"))
      (node (ref "C5") (pin "2") (pinfunction "2_2") (pintype "passive"))
      (node (ref "C6") (pin "2") (pinfunction "2_2") (pintype "passive"))
      (node (ref "C8") (pin "2") (pinfunction "2_2") (pintype "passive"))
      (node (ref "CN1") (pin "2") (pinfunction "+5V_2") (pintype "power_in"))
      (node (ref "CN1") (pin "3") (pinfunction "+5V_3") (pintype "power_in"))
      (node (ref "R1") (pin "2") (pinfunction "2_2") (pintype "passive"))
      (node (ref "R4") (pin "2") (pinfunction "2_2") (pintype "passive"))
      (node (ref "R5") (pin "2") (pinfunction "2_2") (pintype "passive"))
      (node (ref "R6") (pin "1") (pinfunction "1_1") (pintype "passive"))
      (node (ref "R7") (pin "1") (pinfunction "1_1") (pintype "passive"))
      (node (ref "R8") (pin "1") (pinfunction "1_1") (pintype "passive"))
      (node (ref "U1") (pin "10") (pinfunction "~{PRE}_10") (pintype "input"))
      (node (ref "U1") (pin "14") (pinfunction "VCC_14") (pintype "power_in"))
      (node (ref "U10") (pin "16") (pinfunction "VCC_16") (pintype "power_in"))
      (node (ref "U10") (pin "7") (pinfunction "C0_7") (pintype "input"))
      (node (ref "U11") (pin "1") (pinfunction "DIR_1") (pintype "input"))
      (node (ref "U11") (pin "20") (pinfunction "VCC_20") (pintype "passive"))
      (node (ref "U12") (pin "1") (pinfunction "1_1") (pintype "passive"))
      (node (ref "U13") (pin "11") (pinfunction "VCC_11") (pintype "power_in"))
      (node (ref "U14") (pin "1") (pinfunction "DIR_1") (pintype "input"))
      (node (ref "U14") (pin "20") (pinfunction "VCC_20") (pintype "passive"))
      (node (ref "U15") (pin "1") (pinfunction "1_1") (pintype "passive"))
      (node (ref "U2") (pin "14") (pinfunction "VCC_14") (pintype "power_in"))
      (node (ref "U3") (pin "16") (pinfunction "VCC_16") (pintype "power_in"))
      (node (ref "U4") (pin "20") (pinfunction "VCC_20") (pintype "power_in"))
      (node (ref "U5") (pin "13") (pinfunction "~{CLR}_13") (pintype "input"))
      (node (ref "U5") (pin "14") (pinfunction "VCC_14") (pintype "power_in"))
      (node (ref "U5") (pin "2") (pinfunction "D_2") (pintype "input"))
      (node (ref "U6") (pin "14") (pinfunction "VCC_14") (pintype "power_in"))
      (node (ref "U7") (pin "1") (pinfunction "DIR_1") (pintype "input"))
      (node (ref "U7") (pin "20") (pinfunction "VCC_20") (pintype "passive"))
      (node (ref "U8") (pin "1") (pinfunction "1_1") (pintype "passive"))
      (node (ref "U9") (pin "14") (pinfunction "VCC_14") (pintype "power_in"))
    )
    (net (code "98") (name "unconnected-(CN1-~{EXROM}-Pad9)") (class "Default")
      (node (ref "CN1") (pin "9") (pinfunction "~{EXROM}_9") (pintype "input+no_connect"))
    )
    (net (code "99") (name "unconnected-(CN1-~{GAME}-Pad8)") (class "Default")
      (node (ref "CN1") (pin "8") (pinfunction "~{GAME}_8") (pintype "input+no_connect"))
    )
    (net (code "100") (name "unconnected-(CN1-~{IRQ}-Pad4)") (class "Default")
      (node (ref "CN1") (pin "4") (pinfunction "~{IRQ}_4") (pintype "input+no_connect"))
    )
    (net (code "101") (name "unconnected-(CN1-~{I{slash}O2}-Pad10)") (class "Default")
      (node (ref "CN1") (pin "10") (pinfunction "~{I/O2}_10") (pintype "output+no_connect"))
    )
    (net (code "102") (name "unconnected-(CN1-~{NMI}-PadD)") (class "Default")
      (node (ref "CN1") (pin "D") (pinfunction "~{NMI}_D") (pintype "input+no_connect"))
    )
    (net (code "103") (name "unconnected-(CN1-~{ROMH}-PadB)") (class "Default")
      (node (ref "CN1") (pin "B") (pinfunction "~{ROMH}_B") (pintype "output+no_connect"))
    )
    (net (code "104") (name "unconnected-(CN1-~{ROML}-Pad11)") (class "Default")
      (node (ref "CN1") (pin "11") (pinfunction "~{ROML}_11") (pintype "output+no_connect"))
    )
    (net (code "105") (name "unconnected-(U1A-D-Pad2)") (class "Default")
      (node (ref "U1") (pin "2") (pinfunction "D_2") (pintype "input+no_connect"))
    )
    (net (code "106") (name "unconnected-(U1A-Q-Pad5)") (class "Default")
      (node (ref "U1") (pin "5") (pinfunction "Q_5") (pintype "output+no_connect"))
    )
    (net (code "107") (name "unconnected-(U1A-~{PRE}-Pad4)") (class "Default")
      (node (ref "U1") (pin "4") (pinfunction "~{PRE}_4") (pintype "input+no_connect"))
    )
    (net (code "108") (name "unconnected-(U1A-~{Q}-Pad6)") (class "Default")
      (node (ref "U1") (pin "6") (pinfunction "~{Q}_6") (pintype "output+no_connect"))
    )
    (net (code "109") (name "unconnected-(U1B-Q-Pad9)") (class "Default")
      (node (ref "U1") (pin "9") (pinfunction "Q_9") (pintype "output+no_connect"))
    )
    (net (code "110") (name "unconnected-(U3-2Y1-Pad11)") (class "Default")
      (node (ref "U3") (pin "11") (pinfunction "2Y1_11") (pintype "open_collector+no_connect"))
    )
    (net (code "111") (name "unconnected-(U5B-Q-Pad9)") (class "Default")
      (node (ref "U5") (pin "9") (pinfunction "Q_9") (pintype "output+no_connect"))
    )
    (net (code "112") (name "unconnected-(U9A-1Y-Pad3)") (class "Default")
      (node (ref "U9") (pin "3") (pinfunction "1Y_3") (pintype "output+no_connect"))
    )
    (net (code "113") (name "unconnected-(U10-C4-Pad9)") (class "Default")
      (node (ref "U10") (pin "9") (pinfunction "C4_9") (pintype "output+no_connect"))
    )
    (net (code "114") (name "unconnected-(U13-~{HALT}-Pad18)") (class "Default")
      (node (ref "U13") (pin "18") (pinfunction "~{HALT}_18") (pintype "output+no_connect"))
    )
    (net (code "115") (name "unconnected-(U13-~{IOREQ}-Pad20)") (class "Default")
      (node (ref "U13") (pin "20") (pinfunction "~{IOREQ}_20") (pintype "output+no_connect"))
    )
    (net (code "116") (name "unconnected-(U13-~{M1}-Pad27)") (class "Default")
      (node (ref "U13") (pin "27") (pinfunction "~{M1}_27") (pintype "output+no_connect"))
    )
    (net (code "117") (name "unconnected-(U13-~{MREQ}-Pad19)") (class "Default")
      (node (ref "U13") (pin "19") (pinfunction "~{MREQ}_19") (pintype "output+no_connect"))
    )
    (net (code "118") (name "unconnected-(U13-~{RFSH}-Pad28)") (class "Default")
      (node (ref "U13") (pin "28") (pinfunction "~{RFSH}_28") (pintype "output+no_connect"))
    )
  )
)
